# modFOC-ABNenc.net
KiCad netlist of a schematic drawn in Altium Designer
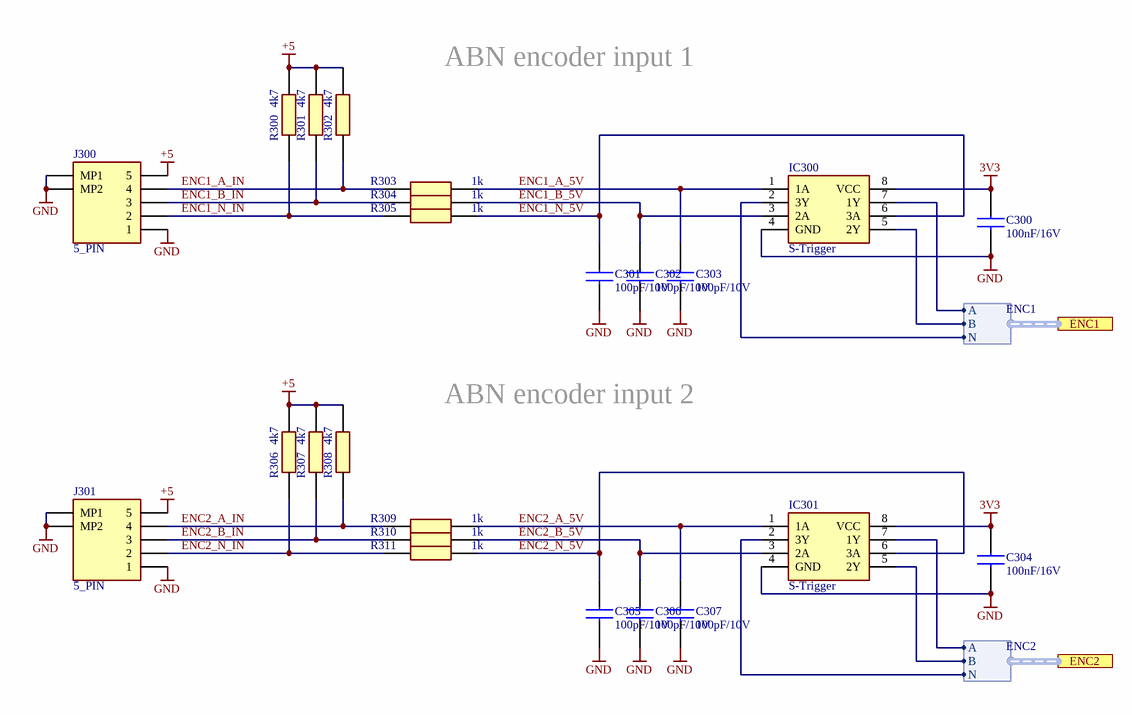
[diagram p0: modFOC-ABNenc.SchDoc]

(export (version "E")
  (design (tool "Eeschema 10.0.6"))
  (components
    (comp (ref "C300")
      (value "100nF/16V")
      (footprint "CAPC1608X97N")
      (description "Capacitor")
      (libsource (lib "Schlib1") (part "C0603"))
    )
    (comp (ref "C301")
      (value "100pF/10V")
      (footprint "CAPC1608X97N")
      (description "Capacitor")
      (libsource (lib "Schlib1") (part "C0603"))
    )
    (comp (ref "C302")
      (value "100pF/10V")
      (footprint "CAPC1608X97N")
      (description "Capacitor")
      (libsource (lib "Schlib1") (part "C0603"))
    )
    (comp (ref "C303")
      (value "100pF/10V")
      (footprint "CAPC1608X97N")
      (description "Capacitor")
      (libsource (lib "Schlib1") (part "C0603"))
    )
    (comp (ref "C304")
      (value "100nF/16V")
      (footprint "CAPC1608X97N")
      (description "Capacitor")
      (libsource (lib "Schlib1") (part "C0603"))
    )
    (comp (ref "C305")
      (value "100pF/10V")
      (footprint "CAPC1608X97N")
      (description "Capacitor")
      (libsource (lib "Schlib1") (part "C0603"))
    )
    (comp (ref "C306")
      (value "100pF/10V")
      (footprint "CAPC1608X97N")
      (description "Capacitor")
      (libsource (lib "Schlib1") (part "C0603"))
    )
    (comp (ref "C307")
      (value "100pF/10V")
      (footprint "CAPC1608X97N")
      (description "Capacitor")
      (libsource (lib "Schlib1") (part "C0603"))
    )
    (comp (ref "IC300")
      (value "S-Trigger")
      (footprint "SOP65P400X110-8N")
      (description "3x Schmitt trigger")
      (fields
        (field (name "MANUFACTURER_PART_NUMBER") "74LVC3G17DP,125")
        (field (name "MOUSER PART NUMBER") "771-LVC3G17DP125")
      )
      (libsource (lib "Schlib1") (part "74LVC3G17DP,125"))
    )
    (comp (ref "IC301")
      (value "S-Trigger")
      (footprint "SOP65P400X110-8N")
      (description "3x Schmitt trigger")
      (fields
        (field (name "MANUFACTURER_PART_NUMBER") "74LVC3G17DP,125")
        (field (name "MOUSER PART NUMBER") "771-LVC3G17DP125")
      )
      (libsource (lib "Schlib1") (part "74LVC3G17DP,125"))
    )
    (comp (ref "J300")
      (value "5_PIN")
      (footprint "DF13A5P125H21")
      (description "Connector")
      (fields
        (field (name "MANUFACTURER_PART_NUMBER") "DF13A-5P-1.25H(21)")
        (field (name "MOUSER PART NUMBER") "798-DF13A5P125H21")
      )
      (libsource (lib "Schlib1") (part "DF13A-5P-1.25H_21_"))
    )
    (comp (ref "J301")
      (value "5_PIN")
      (footprint "DF13A5P125H21")
      (description "Connector")
      (fields
        (field (name "MANUFACTURER_PART_NUMBER") "DF13A-5P-1.25H(21)")
        (field (name "MOUSER PART NUMBER") "798-DF13A5P125H21")
      )
      (libsource (lib "Schlib1") (part "DF13A-5P-1.25H_21_"))
    )
    (comp (ref "R300")
      (value "4k7")
      (footprint "RESC1608X55N")
      (description "Resistor")
      (libsource (lib "Schlib1") (part "R0603"))
    )
    (comp (ref "R301")
      (value "4k7")
      (footprint "RESC1608X55N")
      (description "Resistor")
      (libsource (lib "Schlib1") (part "R0603"))
    )
    (comp (ref "R302")
      (value "4k7")
      (footprint "RESC1608X55N")
      (description "Resistor")
      (libsource (lib "Schlib1") (part "R0603"))
    )
    (comp (ref "R303")
      (value "1k")
      (footprint "RESC1608X55N")
      (description "Resistor")
      (libsource (lib "") (part "R0603_1"))
    )
    (comp (ref "R304")
      (value "1k")
      (footprint "RESC1608X55N")
      (description "Resistor")
      (libsource (lib "") (part "R0603_1"))
    )
    (comp (ref "R305")
      (value "1k")
      (footprint "RESC1608X55N")
      (description "Resistor")
      (libsource (lib "") (part "R0603_1"))
    )
    (comp (ref "R306")
      (value "4k7")
      (footprint "RESC1608X55N")
      (description "Resistor")
      (libsource (lib "Schlib1") (part "R0603"))
    )
    (comp (ref "R307")
      (value "4k7")
      (footprint "RESC1608X55N")
      (description "Resistor")
      (libsource (lib "Schlib1") (part "R0603"))
    )
    (comp (ref "R308")
      (value "4k7")
      (footprint "RESC1608X55N")
      (description "Resistor")
      (libsource (lib "Schlib1") (part "R0603"))
    )
    (comp (ref "R309")
      (value "1k")
      (footprint "RESC1608X55N")
      (description "Resistor")
      (libsource (lib "") (part "R0603_1"))
    )
    (comp (ref "R310")
      (value "1k")
      (footprint "RESC1608X55N")
      (description "Resistor")
      (libsource (lib "") (part "R0603_1"))
    )
    (comp (ref "R311")
      (value "1k")
      (footprint "RESC1608X55N")
      (description "Resistor")
      (libsource (lib "") (part "R0603_1"))
    )
  )
  (nets
    (net (code "3") (name "+5") (class "Default")
      (node (ref "J300") (pin "5") (pinfunction "5_5") (pintype "passive"))
      (node (ref "J301") (pin "5") (pinfunction "5_5") (pintype "passive"))
      (node (ref "R300") (pin "2") (pinfunction "2_2") (pintype "passive"))
      (node (ref "R301") (pin "2") (pinfunction "2_2") (pintype "passive"))
      (node (ref "R302") (pin "2") (pinfunction "2_2") (pintype "passive"))
      (node (ref "R306") (pin "2") (pinfunction "2_2") (pintype "passive"))
      (node (ref "R307") (pin "2") (pinfunction "2_2") (pintype "passive"))
      (node (ref "R308") (pin "2") (pinfunction "2_2") (pintype "passive"))
    )
    (net (code "4") (name "/ENC1_A_5V") (class "Default")
      (node (ref "C303") (pin "1") (pinfunction "1_1") (pintype "passive"))
      (node (ref "IC300") (pin "1") (pinfunction "1A_1") (pintype "passive"))
      (node (ref "R303") (pin "1") (pinfunction "1_1") (pintype "passive"))
    )
    (net (code "5") (name "/ENC1_A_IN") (class "Default")
      (node (ref "J300") (pin "4") (pinfunction "4_4") (pintype "passive"))
      (node (ref "R302") (pin "1") (pinfunction "1_1") (pintype "passive"))
      (node (ref "R303") (pin "2") (pinfunction "2_2") (pintype "passive"))
    )
    (net (code "6") (name "/ENC1_B_5V") (class "Default")
      (node (ref "C302") (pin "1") (pinfunction "1_1") (pintype "passive"))
      (node (ref "IC300") (pin "3") (pinfunction "2A_3") (pintype "passive"))
      (node (ref "R304") (pin "1") (pinfunction "1_1") (pintype "passive"))
    )
    (net (code "7") (name "/ENC1_B_IN") (class "Default")
      (node (ref "J300") (pin "3") (pinfunction "3_3") (pintype "passive"))
      (node (ref "R301") (pin "1") (pinfunction "1_1") (pintype "passive"))
      (node (ref "R304") (pin "2") (pinfunction "2_2") (pintype "passive"))
    )
    (net (code "8") (name "/ENC1_N_5V") (class "Default")
      (node (ref "C301") (pin "1") (pinfunction "1_1") (pintype "passive"))
      (node (ref "IC300") (pin "6") (pinfunction "3A_6") (pintype "passive"))
      (node (ref "R305") (pin "1") (pinfunction "1_1") (pintype "passive"))
    )
    (net (code "9") (name "/ENC1_N_IN") (class "Default")
      (node (ref "J300") (pin "2") (pinfunction "2_2") (pintype "passive"))
      (node (ref "R300") (pin "1") (pinfunction "1_1") (pintype "passive"))
      (node (ref "R305") (pin "2") (pinfunction "2_2") (pintype "passive"))
    )
    (net (code "10") (name "/ENC2_A_5V") (class "Default")
      (node (ref "C307") (pin "1") (pinfunction "1_1") (pintype "passive"))
      (node (ref "IC301") (pin "1") (pinfunction "1A_1") (pintype "passive"))
      (node (ref "R309") (pin "1") (pinfunction "1_1") (pintype "passive"))
    )
    (net (code "11") (name "/ENC2_A_IN") (class "Default")
      (node (ref "J301") (pin "4") (pinfunction "4_4") (pintype "passive"))
      (node (ref "R308") (pin "1") (pinfunction "1_1") (pintype "passive"))
      (node (ref "R309") (pin "2") (pinfunction "2_2") (pintype "passive"))
    )
    (net (code "12") (name "/ENC2_B_5V") (class "Default")
      (node (ref "C306") (pin "1") (pinfunction "1_1") (pintype "passive"))
      (node (ref "IC301") (pin "3") (pinfunction "2A_3") (pintype "passive"))
      (node (ref "R310") (pin "1") (pinfunction "1_1") (pintype "passive"))
    )
    (net (code "13") (name "/ENC2_B_IN") (class "Default")
      (node (ref "J301") (pin "3") (pinfunction "3_3") (pintype "passive"))
      (node (ref "R307") (pin "1") (pinfunction "1_1") (pintype "passive"))
      (node (ref "R310") (pin "2") (pinfunction "2_2") (pintype "passive"))
    )
    (net (code "14") (name "/ENC2_N_5V") (class "Default")
      (node (ref "C305") (pin "1") (pinfunction "1_1") (pintype "passive"))
      (node (ref "IC301") (pin "6") (pinfunction "3A_6") (pintype "passive"))
      (node (ref "R311") (pin "1") (pinfunction "1_1") (pintype "passive"))
    )
    (net (code "15") (name "/ENC2_N_IN") (class "Default")
      (node (ref "J301") (pin "2") (pinfunction "2_2") (pintype "passive"))
      (node (ref "R306") (pin "1") (pinfunction "1_1") (pintype "passive"))
      (node (ref "R311") (pin "2") (pinfunction "2_2") (pintype "passive"))
    )
    (net (code "18") (name "3V3") (class "Default")
      (node (ref "C300") (pin "2") (pinfunction "2_2") (pintype "passive"))
      (node (ref "C304") (pin "2") (pinfunction "2_2") (pintype "passive"))
      (node (ref "IC300") (pin "8") (pinfunction "VCC_8") (pintype "passive"))
      (node (ref "IC301") (pin "8") (pinfunction "VCC_8") (pintype "passive"))
    )
    (net (code "19") (name "GND") (class "Default")
      (node (ref "C300") (pin "1") (pinfunction "1_1") (pintype "passive"))
      (node (ref "C301") (pin "2") (pinfunction "2_2") (pintype "passive"))
      (node (ref "C302") (pin "2") (pinfunction "2_2") (pintype "passive"))
      (node (ref "C303") (pin "2") (pinfunction "2_2") (pintype "passive"))
      (node (ref "C304") (pin "1") (pinfunction "1_1") (pintype "passive"))
      (node (ref "C305") (pin "2") (pinfunction "2_2") (pintype "passive"))
      (node (ref "C306") (pin "2") (pinfunction "2_2") (pintype "passive"))
      (node (ref "C307") (pin "2") (pinfunction "2_2") (pintype "passive"))
      (node (ref "IC300") (pin "4") (pinfunction "GND_4") (pintype "passive"))
      (node (ref "IC301") (pin "4") (pinfunction "GND_4") (pintype "passive"))
      (node (ref "J300") (pin "1") (pinfunction "1_1") (pintype "passive"))
      (node (ref "J300") (pin "MP1") (pinfunction "MP1_MP1") (pintype "passive"))
      (node (ref "J300") (pin "MP2") (pinfunction "MP2_MP2") (pintype "passive"))
      (node (ref "J301") (pin "1") (pinfunction "1_1") (pintype "passive"))
      (node (ref "J301") (pin "MP1") (pinfunction "MP1_MP1") (pintype "passive"))
      (node (ref "J301") (pin "MP2") (pinfunction "MP2_MP2") (pintype "passive"))
    )
    (net (code "20") (name "unconnected-(IC300-1Y-Pad7)") (class "Default")
      (node (ref "IC300") (pin "7") (pinfunction "1Y_7") (pintype "passive"))
    )
    (net (code "21") (name "unconnected-(IC300-2Y-Pad5)") (class "Default")
      (node (ref "IC300") (pin "5") (pinfunction "2Y_5") (pintype "passive"))
    )
    (net (code "22") (name "unconnected-(IC300-3Y-Pad2)") (class "Default")
      (node (ref "IC300") (pin "2") (pinfunction "3Y_2") (pintype "passive"))
    )
    (net (code "23") (name "unconnected-(IC301-1Y-Pad7)") (class "Default")
      (node (ref "IC301") (pin "7") (pinfunction "1Y_7") (pintype "passive"))
    )
    (net (code "24") (name "unconnected-(IC301-2Y-Pad5)") (class "Default")
      (node (ref "IC301") (pin "5") (pinfunction "2Y_5") (pintype "passive"))
    )
    (net (code "25") (name "unconnected-(IC301-3Y-Pad2)") (class "Default")
      (node (ref "IC301") (pin "2") (pinfunction "3Y_2") (pintype "passive"))
    )
  )
)
